# HeaderPins.net
KiCad netlist of a schematic drawn in Altium Designer
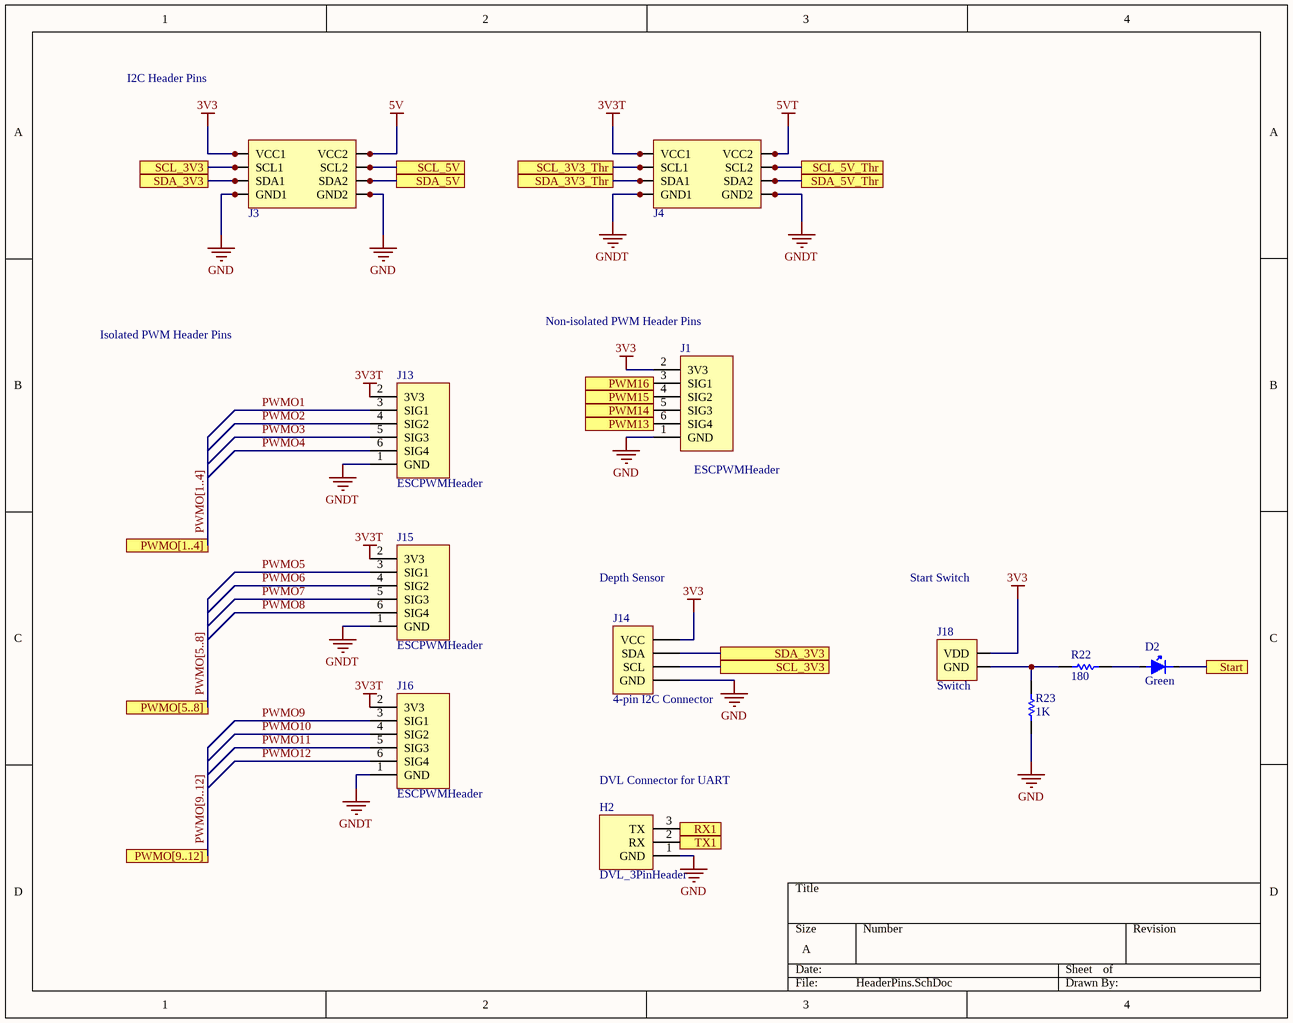
[diagram p0: HeaderPins.SchDoc]

(export (version "E")
  (design (tool "Eeschema 10.0.6"))
  (components
    (comp (ref "D2")
      (value "Green")
      (footprint "LED-D12")
      (description "LED GREEN DIFFUSED 1608 SMD")
      (libsource (lib "Main") (part "SML-D12FWT86"))
    )
    (comp (ref "H2")
      (value "DVL_3PinHeader")
      (footprint "SAMTEC-TSW-103-07-X-S")
      (libsource (lib "Main") (part "DVL_3PinHeader"))
    )
    (comp (ref "J1")
      (value "ESCPWMHeader")
      (footprint "CON12_3X4_TU_TSW_SAI")
      (description "4x3 Header Block")
      (libsource (lib "Main") (part "ESCPWMHeader"))
    )
    (comp (ref "J3")
      (value "i2c-2x2")
      (footprint "37216-62M3-004PL")
      (libsource (lib "Main") (part "i2c-2x2"))
    )
    (comp (ref "J4")
      (value "i2c-2x2")
      (footprint "37216-62M3-004PL")
      (libsource (lib "Main") (part "i2c-2x2"))
    )
    (comp (ref "J13")
      (value "ESCPWMHeader")
      (footprint "37212-62M3-003PL")
      (description "4x3 Header Block")
      (libsource (lib "Main") (part "ESCPWMHeader"))
    )
    (comp (ref "J14")
      (value "4-pin I2C Connector")
      (footprint "CON4_1X4_U_DF13")
      (description "Headers & Wire Housings 1.25MM V PCB HEADER 4P SMT GOLD")
      (libsource (lib "Main") (part "DF13C-4P-1.25V(51)"))
    )
    (comp (ref "J15")
      (value "ESCPWMHeader")
      (footprint "37212-62M3-003PL")
      (description "4x3 Header Block")
      (libsource (lib "Main") (part "ESCPWMHeader"))
    )
    (comp (ref "J16")
      (value "ESCPWMHeader")
      (footprint "37212-62M3-003PL")
      (description "4x3 Header Block")
      (libsource (lib "Main") (part "ESCPWMHeader"))
    )
    (comp (ref "J18")
      (value "Switch")
      (footprint "2PinHeader")
      (libsource (lib "Main") (part "Start_Switch"))
    )
    (comp (ref "R22")
      (value "180")
      (footprint "RESC1609X55X30NL10T20")
      (description "RES 180 OHM 0.1% 1/8W 0603")
      (fields (field (name "TOLERANCE") "1%"))
      (libsource (lib "Main") (part "TNPW0603180RBEEA"))
    )
    (comp (ref "R23")
      (value "1K")
      (footprint "RESC1609X55X30NL10T20")
      (description "RES 1K OHM 0.1% 1/8W 0603")
      (fields (field (name "TOLERANCE") "1%"))
      (libsource (lib "Main") (part "TNPW06031K00BEEA"))
    )
  )
  (nets
    (net (code "1") (name "/PWM13") (class "Default")
      (node (ref "J1") (pin "6") (pinfunction "SIG4_6") (pintype "passive"))
    )
    (net (code "2") (name "/PWM14") (class "Default")
      (node (ref "J1") (pin "5") (pinfunction "SIG3_5") (pintype "passive"))
    )
    (net (code "3") (name "/PWM15") (class "Default")
      (node (ref "J1") (pin "4") (pinfunction "SIG2_4") (pintype "passive"))
    )
    (net (code "4") (name "/PWM16") (class "Default")
      (node (ref "J1") (pin "3") (pinfunction "SIG1_3") (pintype "passive"))
    )
    (net (code "5") (name "/PWMO1") (class "Default")
      (node (ref "J13") (pin "3") (pinfunction "SIG1_3") (pintype "passive"))
    )
    (net (code "6") (name "/PWMO2") (class "Default")
      (node (ref "J13") (pin "4") (pinfunction "SIG2_4") (pintype "passive"))
    )
    (net (code "7") (name "/PWMO3") (class "Default")
      (node (ref "J13") (pin "5") (pinfunction "SIG3_5") (pintype "passive"))
    )
    (net (code "8") (name "/PWMO4") (class "Default")
      (node (ref "J13") (pin "6") (pinfunction "SIG4_6") (pintype "passive"))
    )
    (net (code "9") (name "/PWMO5") (class "Default")
      (node (ref "J15") (pin "3") (pinfunction "SIG1_3") (pintype "passive"))
    )
    (net (code "10") (name "/PWMO6") (class "Default")
      (node (ref "J15") (pin "4") (pinfunction "SIG2_4") (pintype "passive"))
    )
    (net (code "11") (name "/PWMO7") (class "Default")
      (node (ref "J15") (pin "5") (pinfunction "SIG3_5") (pintype "passive"))
    )
    (net (code "12") (name "/PWMO8") (class "Default")
      (node (ref "J15") (pin "6") (pinfunction "SIG4_6") (pintype "passive"))
    )
    (net (code "13") (name "/PWMO9") (class "Default")
      (node (ref "J16") (pin "3") (pinfunction "SIG1_3") (pintype "passive"))
    )
    (net (code "14") (name "/PWMO10") (class "Default")
      (node (ref "J16") (pin "4") (pinfunction "SIG2_4") (pintype "passive"))
    )
    (net (code "15") (name "/PWMO11") (class "Default")
      (node (ref "J16") (pin "5") (pinfunction "SIG3_5") (pintype "passive"))
    )
    (net (code "16") (name "/PWMO12") (class "Default")
      (node (ref "J16") (pin "6") (pinfunction "SIG4_6") (pintype "passive"))
    )
    (net (code "20") (name "/RX1") (class "Default")
      (node (ref "H2") (pin "3") (pinfunction "TX_3") (pintype "passive"))
    )
    (net (code "21") (name "/SCL_3V3") (class "Default")
      (node (ref "J14") (pin "3") (pinfunction "SCL_3") (pintype "passive"))
      (node (ref "J3") (pin "2") (pintype "passive"))
      (node (ref "J3") (pin "6") (pinfunction "SCL1_6") (pintype "passive"))
    )
    (net (code "22") (name "/SCL_3V3_Thr") (class "Default")
      (node (ref "J4") (pin "2") (pintype "passive"))
      (node (ref "J4") (pin "6") (pinfunction "SCL1_6") (pintype "passive"))
    )
    (net (code "23") (name "/SCL_5V") (class "Default")
      (node (ref "J3") (pin "10") (pintype "passive"))
      (node (ref "J3") (pin "14") (pinfunction "SCL2_14") (pintype "passive"))
    )
    (net (code "24") (name "/SCL_5V_Thr") (class "Default")
      (node (ref "J4") (pin "10") (pintype "passive"))
      (node (ref "J4") (pin "14") (pinfunction "SCL2_14") (pintype "passive"))
    )
    (net (code "25") (name "/SDA_3V3") (class "Default")
      (node (ref "J14") (pin "2") (pinfunction "SDA_2") (pintype "passive"))
      (node (ref "J3") (pin "3") (pintype "passive"))
      (node (ref "J3") (pin "7") (pinfunction "SDA1_7") (pintype "passive"))
    )
    (net (code "26") (name "/SDA_3V3_Thr") (class "Default")
      (node (ref "J4") (pin "3") (pintype "passive"))
      (node (ref "J4") (pin "7") (pinfunction "SDA1_7") (pintype "passive"))
    )
    (net (code "27") (name "/SDA_5V") (class "Default")
      (node (ref "J3") (pin "11") (pintype "passive"))
      (node (ref "J3") (pin "15") (pinfunction "SDA2_15") (pintype "passive"))
    )
    (net (code "28") (name "/SDA_5V_Thr") (class "Default")
      (node (ref "J4") (pin "11") (pintype "passive"))
      (node (ref "J4") (pin "15") (pinfunction "SDA2_15") (pintype "passive"))
    )
    (net (code "29") (name "/Start") (class "Default")
      (node (ref "D2") (pin "C") (pinfunction "C_C") (pintype "passive"))
    )
    (net (code "30") (name "/TX1") (class "Default")
      (node (ref "H2") (pin "2") (pinfunction "RX_2") (pintype "passive"))
    )
    (net (code "31") (name "3V3") (class "Default")
      (node (ref "J1") (pin "2") (pinfunction "3V3_2") (pintype "passive"))
      (node (ref "J14") (pin "1") (pinfunction "VCC_1") (pintype "passive"))
      (node (ref "J18") (pin "2") (pinfunction "VDD_2") (pintype "passive"))
      (node (ref "J3") (pin "1") (pintype "passive"))
      (node (ref "J3") (pin "5") (pinfunction "VCC1_5") (pintype "passive"))
    )
    (net (code "32") (name "3V3T") (class "Default")
      (node (ref "J13") (pin "2") (pinfunction "3V3_2") (pintype "passive"))
      (node (ref "J15") (pin "2") (pinfunction "3V3_2") (pintype "passive"))
      (node (ref "J16") (pin "2") (pinfunction "3V3_2") (pintype "passive"))
      (node (ref "J4") (pin "1") (pintype "passive"))
      (node (ref "J4") (pin "5") (pinfunction "VCC1_5") (pintype "passive"))
    )
    (net (code "33") (name "5V") (class "Default")
      (node (ref "J3") (pin "13") (pinfunction "VCC2_13") (pintype "passive"))
      (node (ref "J3") (pin "9") (pintype "passive"))
    )
    (net (code "34") (name "5VT") (class "Default")
      (node (ref "J4") (pin "13") (pinfunction "VCC2_13") (pintype "passive"))
      (node (ref "J4") (pin "9") (pintype "passive"))
    )
    (net (code "35") (name "GND") (class "Default")
      (node (ref "H2") (pin "1") (pinfunction "GND_1") (pintype "passive"))
      (node (ref "J1") (pin "1") (pinfunction "GND_1") (pintype "passive"))
      (node (ref "J14") (pin "4") (pinfunction "GND_4") (pintype "passive"))
      (node (ref "J3") (pin "12") (pintype "passive"))
      (node (ref "J3") (pin "16") (pinfunction "GND2_16") (pintype "passive"))
      (node (ref "J3") (pin "4") (pintype "passive"))
      (node (ref "J3") (pin "8") (pinfunction "GND1_8") (pintype "passive"))
      (node (ref "R23") (pin "1") (pinfunction "1_1") (pintype "passive"))
    )
    (net (code "36") (name "GNDT") (class "Default")
      (node (ref "J13") (pin "1") (pinfunction "GND_1") (pintype "passive"))
      (node (ref "J15") (pin "1") (pinfunction "GND_1") (pintype "passive"))
      (node (ref "J16") (pin "1") (pinfunction "GND_1") (pintype "passive"))
      (node (ref "J4") (pin "12") (pintype "passive"))
      (node (ref "J4") (pin "16") (pinfunction "GND2_16") (pintype "passive"))
      (node (ref "J4") (pin "4") (pintype "passive"))
      (node (ref "J4") (pin "8") (pinfunction "GND1_8") (pintype "passive"))
    )
    (net (code "37") (name "Net-(D2-PadA)") (class "Default")
      (node (ref "D2") (pin "A") (pinfunction "A_A") (pintype "passive"))
      (node (ref "R22") (pin "1") (pinfunction "1_1") (pintype "passive"))
    )
    (net (code "38") (name "Net-(J18-GND)") (class "Default")
      (node (ref "J18") (pin "1") (pinfunction "GND_1") (pintype "passive"))
      (node (ref "R22") (pin "2") (pinfunction "2_2") (pintype "passive"))
      (node (ref "R23") (pin "2") (pinfunction "2_2") (pintype "passive"))
    )
  )
)
